# RGB_LED_2.net
KiCad netlist of a schematic drawn in Altium Designer
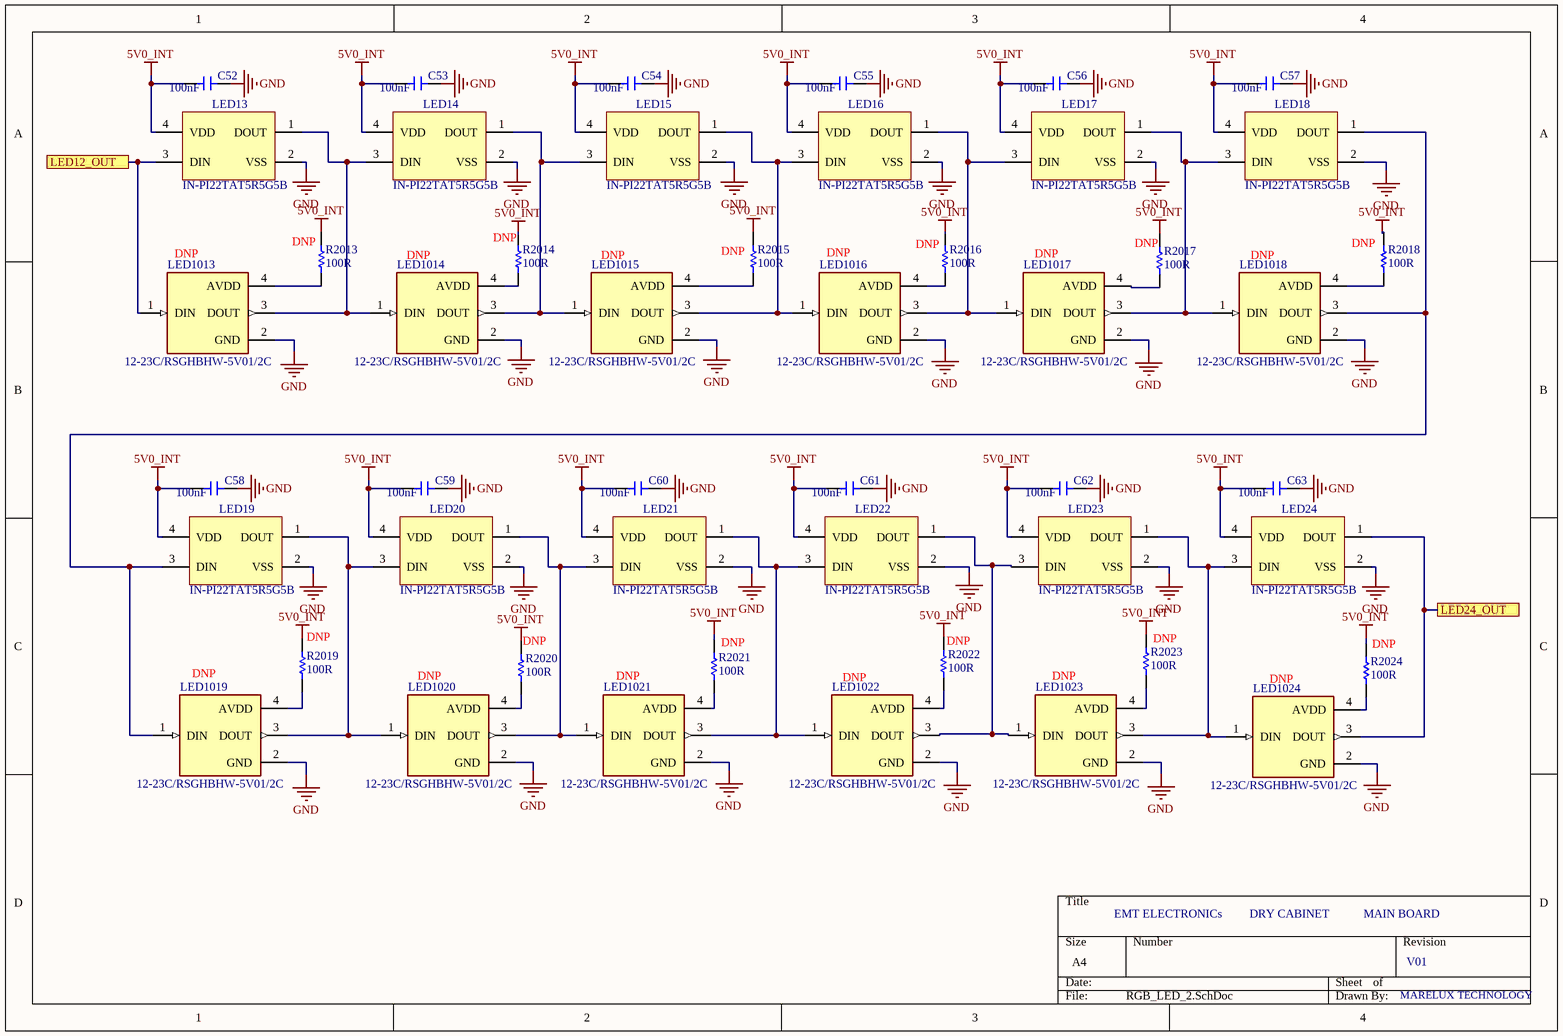
[diagram p0: RGB_LED_2.SchDoc]

(export (version "E")
  (design (tool "Eeschema 10.0.6"))
  (components
    (comp (ref "C52")
      (value "100nF")
      (footprint "MareLux24Lib:CAP_0402_CER")
      (description "100nF 0402 Ceramic Capacitor")
      (fields (field (name "PART NUMBER") "CL05B104KP5NNNC") (field (name "VOLTAGE") "10V"))
      (libsource (lib "MareLux24Lib") (part "CAP_GEN_CER"))
    )
    (comp (ref "C53")
      (value "100nF")
      (footprint "MareLux24Lib:CAP_0402_CER")
      (description "100nF 0402 Ceramic Capacitor")
      (fields (field (name "PART NUMBER") "CL05B104KP5NNNC") (field (name "VOLTAGE") "10V"))
      (libsource (lib "MareLux24Lib") (part "CAP_GEN_CER"))
    )
    (comp (ref "C54")
      (value "100nF")
      (footprint "MareLux24Lib:CAP_0402_CER")
      (description "100nF 0402 Ceramic Capacitor")
      (fields (field (name "PART NUMBER") "CL05B104KP5NNNC") (field (name "VOLTAGE") "10V"))
      (libsource (lib "MareLux24Lib") (part "CAP_GEN_CER"))
    )
    (comp (ref "C55")
      (value "100nF")
      (footprint "MareLux24Lib:CAP_0402_CER")
      (description "100nF 0402 Ceramic Capacitor")
      (fields (field (name "PART NUMBER") "CL05B104KP5NNNC") (field (name "VOLTAGE") "10V"))
      (libsource (lib "MareLux24Lib") (part "CAP_GEN_CER"))
    )
    (comp (ref "C56")
      (value "100nF")
      (footprint "MareLux24Lib:CAP_0402_CER")
      (description "100nF 0402 Ceramic Capacitor")
      (fields (field (name "PART NUMBER") "CL05B104KP5NNNC") (field (name "VOLTAGE") "10V"))
      (libsource (lib "MareLux24Lib") (part "CAP_GEN_CER"))
    )
    (comp (ref "C57")
      (value "100nF")
      (footprint "MareLux24Lib:CAP_0402_CER")
      (description "100nF 0402 Ceramic Capacitor")
      (fields (field (name "PART NUMBER") "CL05B104KP5NNNC") (field (name "VOLTAGE") "10V"))
      (libsource (lib "MareLux24Lib") (part "CAP_GEN_CER"))
    )
    (comp (ref "C58")
      (value "100nF")
      (footprint "MareLux24Lib:CAP_0402_CER")
      (description "100nF 0402 Ceramic Capacitor")
      (fields (field (name "PART NUMBER") "CL05B104KP5NNNC") (field (name "VOLTAGE") "10V"))
      (libsource (lib "MareLux24Lib") (part "CAP_GEN_CER"))
    )
    (comp (ref "C59")
      (value "100nF")
      (footprint "MareLux24Lib:CAP_0402_CER")
      (description "100nF 0402 Ceramic Capacitor")
      (fields (field (name "PART NUMBER") "CL05B104KP5NNNC") (field (name "VOLTAGE") "10V"))
      (libsource (lib "MareLux24Lib") (part "CAP_GEN_CER"))
    )
    (comp (ref "C60")
      (value "100nF")
      (footprint "MareLux24Lib:CAP_0402_CER")
      (description "100nF 0402 Ceramic Capacitor")
      (fields (field (name "PART NUMBER") "CL05B104KP5NNNC") (field (name "VOLTAGE") "10V"))
      (libsource (lib "MareLux24Lib") (part "CAP_GEN_CER"))
    )
    (comp (ref "C61")
      (value "100nF")
      (footprint "MareLux24Lib:CAP_0402_CER")
      (description "100nF 0402 Ceramic Capacitor")
      (fields (field (name "PART NUMBER") "CL05B104KP5NNNC") (field (name "VOLTAGE") "10V"))
      (libsource (lib "MareLux24Lib") (part "CAP_GEN_CER"))
    )
    (comp (ref "C62")
      (value "100nF")
      (footprint "MareLux24Lib:CAP_0402_CER")
      (description "100nF 0402 Ceramic Capacitor")
      (fields (field (name "PART NUMBER") "CL05B104KP5NNNC") (field (name "VOLTAGE") "10V"))
      (libsource (lib "MareLux24Lib") (part "CAP_GEN_CER"))
    )
    (comp (ref "C63")
      (value "100nF")
      (footprint "MareLux24Lib:CAP_0402_CER")
      (description "100nF 0402 Ceramic Capacitor")
      (fields (field (name "PART NUMBER") "CL05B104KP5NNNC") (field (name "VOLTAGE") "10V"))
      (libsource (lib "MareLux24Lib") (part "CAP_GEN_CER"))
    )
    (comp (ref "LED13")
      (value "IN-PI22TAT5R5G5B")
      (footprint "RGB_IN-PI22TAT5R5G5B")
      (description "ADDRESS LED DISCRETE SERIAL RGB")
      (fields (field (name "MANUFACTURER") "Inolux"))
      (libsource (lib "MareLux24Lib") (part "IN-PI22TAT5R5G5B"))
    )
    (comp (ref "LED14")
      (value "IN-PI22TAT5R5G5B")
      (footprint "RGB_IN-PI22TAT5R5G5B")
      (description "ADDRESS LED DISCRETE SERIAL RGB")
      (fields (field (name "MANUFACTURER") "Inolux"))
      (libsource (lib "MareLux24Lib") (part "IN-PI22TAT5R5G5B"))
    )
    (comp (ref "LED15")
      (value "IN-PI22TAT5R5G5B")
      (footprint "RGB_IN-PI22TAT5R5G5B")
      (description "ADDRESS LED DISCRETE SERIAL RGB")
      (fields (field (name "MANUFACTURER") "Inolux"))
      (libsource (lib "MareLux24Lib") (part "IN-PI22TAT5R5G5B"))
    )
    (comp (ref "LED16")
      (value "IN-PI22TAT5R5G5B")
      (footprint "RGB_IN-PI22TAT5R5G5B")
      (description "ADDRESS LED DISCRETE SERIAL RGB")
      (fields (field (name "MANUFACTURER") "Inolux"))
      (libsource (lib "MareLux24Lib") (part "IN-PI22TAT5R5G5B"))
    )
    (comp (ref "LED17")
      (value "IN-PI22TAT5R5G5B")
      (footprint "RGB_IN-PI22TAT5R5G5B")
      (description "ADDRESS LED DISCRETE SERIAL RGB")
      (fields (field (name "MANUFACTURER") "Inolux"))
      (libsource (lib "MareLux24Lib") (part "IN-PI22TAT5R5G5B"))
    )
    (comp (ref "LED18")
      (value "IN-PI22TAT5R5G5B")
      (footprint "RGB_IN-PI22TAT5R5G5B")
      (description "ADDRESS LED DISCRETE SERIAL RGB")
      (fields (field (name "MANUFACTURER") "Inolux"))
      (libsource (lib "MareLux24Lib") (part "IN-PI22TAT5R5G5B"))
    )
    (comp (ref "LED19")
      (value "IN-PI22TAT5R5G5B")
      (footprint "RGB_IN-PI22TAT5R5G5B")
      (description "ADDRESS LED DISCRETE SERIAL RGB")
      (fields (field (name "MANUFACTURER") "Inolux"))
      (libsource (lib "MareLux24Lib") (part "IN-PI22TAT5R5G5B"))
    )
    (comp (ref "LED20")
      (value "IN-PI22TAT5R5G5B")
      (footprint "RGB_IN-PI22TAT5R5G5B")
      (description "ADDRESS LED DISCRETE SERIAL RGB")
      (fields (field (name "MANUFACTURER") "Inolux"))
      (libsource (lib "MareLux24Lib") (part "IN-PI22TAT5R5G5B"))
    )
    (comp (ref "LED21")
      (value "IN-PI22TAT5R5G5B")
      (footprint "RGB_IN-PI22TAT5R5G5B")
      (description "ADDRESS LED DISCRETE SERIAL RGB")
      (fields (field (name "MANUFACTURER") "Inolux"))
      (libsource (lib "MareLux24Lib") (part "IN-PI22TAT5R5G5B"))
    )
    (comp (ref "LED22")
      (value "IN-PI22TAT5R5G5B")
      (footprint "RGB_IN-PI22TAT5R5G5B")
      (description "ADDRESS LED DISCRETE SERIAL RGB")
      (fields (field (name "MANUFACTURER") "Inolux"))
      (libsource (lib "MareLux24Lib") (part "IN-PI22TAT5R5G5B"))
    )
    (comp (ref "LED23")
      (value "IN-PI22TAT5R5G5B")
      (footprint "RGB_IN-PI22TAT5R5G5B")
      (description "ADDRESS LED DISCRETE SERIAL RGB")
      (fields (field (name "MANUFACTURER") "Inolux"))
      (libsource (lib "MareLux24Lib") (part "IN-PI22TAT5R5G5B"))
    )
    (comp (ref "LED24")
      (value "IN-PI22TAT5R5G5B")
      (footprint "RGB_IN-PI22TAT5R5G5B")
      (description "ADDRESS LED DISCRETE SERIAL RGB")
      (fields (field (name "MANUFACTURER") "Inolux"))
      (libsource (lib "MareLux24Lib") (part "IN-PI22TAT5R5G5B"))
    )
    (comp (ref "LED1013")
      (value "12-23C/RSGHBHW-5V01/2C")
      (footprint "LED_12-23C/RSGHBHW-5V01/2C")
      (fields (field (name "MF") "Everlight Electronics Co Ltd") (field (name "PLACE") "DNP"))
      (libsource (lib "12-23C_RSGHBHW-5V01_2C") (part "12-23C/RSGHBHW-5V01/2C"))
    )
    (comp (ref "LED1014")
      (value "12-23C/RSGHBHW-5V01/2C")
      (footprint "LED_12-23C/RSGHBHW-5V01/2C")
      (fields (field (name "MF") "Everlight Electronics Co Ltd") (field (name "PLACE") "DNP"))
      (libsource (lib "12-23C_RSGHBHW-5V01_2C") (part "12-23C/RSGHBHW-5V01/2C"))
    )
    (comp (ref "LED1015")
      (value "12-23C/RSGHBHW-5V01/2C")
      (footprint "LED_12-23C/RSGHBHW-5V01/2C")
      (fields (field (name "MF") "Everlight Electronics Co Ltd") (field (name "PLACE") "DNP"))
      (libsource (lib "12-23C_RSGHBHW-5V01_2C") (part "12-23C/RSGHBHW-5V01/2C"))
    )
    (comp (ref "LED1016")
      (value "12-23C/RSGHBHW-5V01/2C")
      (footprint "LED_12-23C/RSGHBHW-5V01/2C")
      (fields (field (name "MF") "Everlight Electronics Co Ltd") (field (name "PLACE") "DNP"))
      (libsource (lib "12-23C_RSGHBHW-5V01_2C") (part "12-23C/RSGHBHW-5V01/2C"))
    )
    (comp (ref "LED1017")
      (value "12-23C/RSGHBHW-5V01/2C")
      (footprint "LED_12-23C/RSGHBHW-5V01/2C")
      (fields (field (name "MF") "Everlight Electronics Co Ltd") (field (name "PLACE") "DNP"))
      (libsource (lib "12-23C_RSGHBHW-5V01_2C") (part "12-23C/RSGHBHW-5V01/2C"))
    )
    (comp (ref "LED1018")
      (value "12-23C/RSGHBHW-5V01/2C")
      (footprint "LED_12-23C/RSGHBHW-5V01/2C")
      (fields (field (name "MF") "Everlight Electronics Co Ltd") (field (name "PLACE") "DNP"))
      (libsource (lib "12-23C_RSGHBHW-5V01_2C") (part "12-23C/RSGHBHW-5V01/2C"))
    )
    (comp (ref "LED1019")
      (value "12-23C/RSGHBHW-5V01/2C")
      (footprint "LED_12-23C/RSGHBHW-5V01/2C")
      (fields (field (name "MF") "Everlight Electronics Co Ltd") (field (name "PLACE") "DNP"))
      (libsource (lib "12-23C_RSGHBHW-5V01_2C") (part "12-23C/RSGHBHW-5V01/2C"))
    )
    (comp (ref "LED1020")
      (value "12-23C/RSGHBHW-5V01/2C")
      (footprint "LED_12-23C/RSGHBHW-5V01/2C")
      (fields (field (name "MF") "Everlight Electronics Co Ltd") (field (name "PLACE") "DNP"))
      (libsource (lib "12-23C_RSGHBHW-5V01_2C") (part "12-23C/RSGHBHW-5V01/2C"))
    )
    (comp (ref "LED1021")
      (value "12-23C/RSGHBHW-5V01/2C")
      (footprint "LED_12-23C/RSGHBHW-5V01/2C")
      (fields (field (name "MF") "Everlight Electronics Co Ltd") (field (name "PLACE") "DNP"))
      (libsource (lib "12-23C_RSGHBHW-5V01_2C") (part "12-23C/RSGHBHW-5V01/2C"))
    )
    (comp (ref "LED1022")
      (value "12-23C/RSGHBHW-5V01/2C")
      (footprint "LED_12-23C/RSGHBHW-5V01/2C")
      (fields (field (name "MF") "Everlight Electronics Co Ltd") (field (name "PLACE") "DNP"))
      (libsource (lib "12-23C_RSGHBHW-5V01_2C") (part "12-23C/RSGHBHW-5V01/2C"))
    )
    (comp (ref "LED1023")
      (value "12-23C/RSGHBHW-5V01/2C")
      (footprint "LED_12-23C/RSGHBHW-5V01/2C")
      (fields (field (name "MF") "Everlight Electronics Co Ltd") (field (name "PLACE") "DNP"))
      (libsource (lib "12-23C_RSGHBHW-5V01_2C") (part "12-23C/RSGHBHW-5V01/2C"))
    )
    (comp (ref "LED1024")
      (value "12-23C/RSGHBHW-5V01/2C")
      (footprint "LED_12-23C/RSGHBHW-5V01/2C")
      (fields (field (name "MF") "Everlight Electronics Co Ltd") (field (name "PLACE") "DNP"))
      (libsource (lib "12-23C_RSGHBHW-5V01_2C") (part "12-23C/RSGHBHW-5V01/2C"))
    )
    (comp (ref "R2013")
      (value "100R")
      (footprint "MareLux24Lib:RES_0402_SMD")
      (description "Generic Chip Res 100R")
      (fields
        (field (name "PART NUMBER") "RMCF0402JT100R")
        (field (name "TOLERANCE") "5 %")
        (field (name "PLACE") "DNP")
      )
      (libsource (lib "MareLux24Lib") (part "RES_GEN_SMD"))
    )
    (comp (ref "R2014")
      (value "100R")
      (footprint "MareLux24Lib:RES_0402_SMD")
      (description "Generic Chip Res 100R")
      (fields
        (field (name "PART NUMBER") "RMCF0402JT100R")
        (field (name "TOLERANCE") "5 %")
        (field (name "PLACE") "DNP")
      )
      (libsource (lib "MareLux24Lib") (part "RES_GEN_SMD"))
    )
    (comp (ref "R2015")
      (value "100R")
      (footprint "MareLux24Lib:RES_0402_SMD")
      (description "Generic Chip Res 100R")
      (fields
        (field (name "PART NUMBER") "RMCF0402JT100R")
        (field (name "TOLERANCE") "5 %")
        (field (name "PLACE") "DNP")
      )
      (libsource (lib "MareLux24Lib") (part "RES_GEN_SMD"))
    )
    (comp (ref "R2016")
      (value "100R")
      (footprint "MareLux24Lib:RES_0402_SMD")
      (description "Generic Chip Res 100R")
      (fields
        (field (name "PART NUMBER") "RMCF0402JT100R")
        (field (name "TOLERANCE") "5 %")
        (field (name "PLACE") "DNP")
      )
      (libsource (lib "MareLux24Lib") (part "RES_GEN_SMD"))
    )
    (comp (ref "R2017")
      (value "100R")
      (footprint "MareLux24Lib:RES_0402_SMD")
      (description "Generic Chip Res 100R")
      (fields
        (field (name "PART NUMBER") "RMCF0402JT100R")
        (field (name "TOLERANCE") "5 %")
        (field (name "PLACE") "DNP")
      )
      (libsource (lib "MareLux24Lib") (part "RES_GEN_SMD"))
    )
    (comp (ref "R2018")
      (value "100R")
      (footprint "MareLux24Lib:RES_0402_SMD")
      (description "Generic Chip Res 100R")
      (fields
        (field (name "PART NUMBER") "RMCF0402JT100R")
        (field (name "TOLERANCE") "5 %")
        (field (name "PLACE") "DNP")
      )
      (libsource (lib "MareLux24Lib") (part "RES_GEN_SMD"))
    )
    (comp (ref "R2019")
      (value "100R")
      (footprint "MareLux24Lib:RES_0402_SMD")
      (description "Generic Chip Res 100R")
      (fields
        (field (name "PART NUMBER") "RMCF0402JT100R")
        (field (name "TOLERANCE") "5 %")
        (field (name "PLACE") "DNP")
      )
      (libsource (lib "MareLux24Lib") (part "RES_GEN_SMD"))
    )
    (comp (ref "R2020")
      (value "100R")
      (footprint "MareLux24Lib:RES_0402_SMD")
      (description "Generic Chip Res 100R")
      (fields
        (field (name "PART NUMBER") "RMCF0402JT100R")
        (field (name "TOLERANCE") "5 %")
        (field (name "PLACE") "DNP")
      )
      (libsource (lib "MareLux24Lib") (part "RES_GEN_SMD"))
    )
    (comp (ref "R2021")
      (value "100R")
      (footprint "MareLux24Lib:RES_0402_SMD")
      (description "Generic Chip Res 100R")
      (fields
        (field (name "PART NUMBER") "RMCF0402JT100R")
        (field (name "TOLERANCE") "5 %")
        (field (name "PLACE") "DNP")
      )
      (libsource (lib "MareLux24Lib") (part "RES_GEN_SMD"))
    )
    (comp (ref "R2022")
      (value "100R")
      (footprint "MareLux24Lib:RES_0402_SMD")
      (description "Generic Chip Res 100R")
      (fields
        (field (name "PART NUMBER") "RMCF0402JT100R")
        (field (name "TOLERANCE") "5 %")
        (field (name "PLACE") "DNP")
      )
      (libsource (lib "MareLux24Lib") (part "RES_GEN_SMD"))
    )
    (comp (ref "R2023")
      (value "100R")
      (footprint "MareLux24Lib:RES_0402_SMD")
      (description "Generic Chip Res 100R")
      (fields
        (field (name "PART NUMBER") "RMCF0402JT100R")
        (field (name "TOLERANCE") "5 %")
        (field (name "PLACE") "DNP")
      )
      (libsource (lib "MareLux24Lib") (part "RES_GEN_SMD"))
    )
    (comp (ref "R2024")
      (value "100R")
      (footprint "MareLux24Lib:RES_0402_SMD")
      (description "Generic Chip Res 100R")
      (fields
        (field (name "PART NUMBER") "RMCF0402JT100R")
        (field (name "TOLERANCE") "5 %")
        (field (name "PLACE") "DNP")
      )
      (libsource (lib "MareLux24Lib") (part "RES_GEN_SMD"))
    )
  )
  (nets
    (net (code "1") (name "/LED12_OUT") (class "Default")
      (node (ref "LED1013") (pin "1") (pinfunction "DIN_1") (pintype "input"))
      (node (ref "LED13") (pin "3") (pinfunction "DIN_3") (pintype "passive"))
    )
    (net (code "2") (name "/LED24_OUT") (class "Default")
      (node (ref "LED1024") (pin "3") (pinfunction "DOUT_3") (pintype "output"))
      (node (ref "LED24") (pin "1") (pinfunction "DOUT_1") (pintype "passive"))
    )
    (net (code "3") (name "5V0_INT") (class "Default")
      (node (ref "C52") (pin "2") (pinfunction "2_2") (pintype "passive"))
      (node (ref "C53") (pin "2") (pinfunction "2_2") (pintype "passive"))
      (node (ref "C54") (pin "2") (pinfunction "2_2") (pintype "passive"))
      (node (ref "C55") (pin "2") (pinfunction "2_2") (pintype "passive"))
      (node (ref "C56") (pin "2") (pinfunction "2_2") (pintype "passive"))
      (node (ref "C57") (pin "2") (pinfunction "2_2") (pintype "passive"))
      (node (ref "C58") (pin "2") (pinfunction "2_2") (pintype "passive"))
      (node (ref "C59") (pin "2") (pinfunction "2_2") (pintype "passive"))
      (node (ref "C60") (pin "2") (pinfunction "2_2") (pintype "passive"))
      (node (ref "C61") (pin "2") (pinfunction "2_2") (pintype "passive"))
      (node (ref "C62") (pin "2") (pinfunction "2_2") (pintype "passive"))
      (node (ref "C63") (pin "2") (pinfunction "2_2") (pintype "passive"))
      (node (ref "LED13") (pin "4") (pinfunction "VDD_4") (pintype "passive"))
      (node (ref "LED14") (pin "4") (pinfunction "VDD_4") (pintype "passive"))
      (node (ref "LED15") (pin "4") (pinfunction "VDD_4") (pintype "passive"))
      (node (ref "LED16") (pin "4") (pinfunction "VDD_4") (pintype "passive"))
      (node (ref "LED17") (pin "4") (pinfunction "VDD_4") (pintype "passive"))
      (node (ref "LED18") (pin "4") (pinfunction "VDD_4") (pintype "passive"))
      (node (ref "LED19") (pin "4") (pinfunction "VDD_4") (pintype "passive"))
      (node (ref "LED20") (pin "4") (pinfunction "VDD_4") (pintype "passive"))
      (node (ref "LED21") (pin "4") (pinfunction "VDD_4") (pintype "passive"))
      (node (ref "LED22") (pin "4") (pinfunction "VDD_4") (pintype "passive"))
      (node (ref "LED23") (pin "4") (pinfunction "VDD_4") (pintype "passive"))
      (node (ref "LED24") (pin "4") (pinfunction "VDD_4") (pintype "passive"))
      (node (ref "R2013") (pin "1") (pinfunction "1_1") (pintype "passive"))
      (node (ref "R2014") (pin "1") (pinfunction "1_1") (pintype "passive"))
      (node (ref "R2015") (pin "1") (pinfunction "1_1") (pintype "passive"))
      (node (ref "R2016") (pin "1") (pinfunction "1_1") (pintype "passive"))
      (node (ref "R2017") (pin "1") (pinfunction "1_1") (pintype "passive"))
      (node (ref "R2018") (pin "1") (pinfunction "1_1") (pintype "passive"))
      (node (ref "R2019") (pin "1") (pinfunction "1_1") (pintype "passive"))
      (node (ref "R2020") (pin "1") (pinfunction "1_1") (pintype "passive"))
      (node (ref "R2021") (pin "1") (pinfunction "1_1") (pintype "passive"))
      (node (ref "R2022") (pin "1") (pinfunction "1_1") (pintype "passive"))
      (node (ref "R2023") (pin "1") (pinfunction "1_1") (pintype "passive"))
      (node (ref "R2024") (pin "1") (pinfunction "1_1") (pintype "passive"))
    )
    (net (code "4") (name "GND") (class "Default")
      (node (ref "C52") (pin "1") (pinfunction "1_1") (pintype "passive"))
      (node (ref "C53") (pin "1") (pinfunction "1_1") (pintype "passive"))
      (node (ref "C54") (pin "1") (pinfunction "1_1") (pintype "passive"))
      (node (ref "C55") (pin "1") (pinfunction "1_1") (pintype "passive"))
      (node (ref "C56") (pin "1") (pinfunction "1_1") (pintype "passive"))
      (node (ref "C57") (pin "1") (pinfunction "1_1") (pintype "passive"))
      (node (ref "C58") (pin "1") (pinfunction "1_1") (pintype "passive"))
      (node (ref "C59") (pin "1") (pinfunction "1_1") (pintype "passive"))
      (node (ref "C60") (pin "1") (pinfunction "1_1") (pintype "passive"))
      (node (ref "C61") (pin "1") (pinfunction "1_1") (pintype "passive"))
      (node (ref "C62") (pin "1") (pinfunction "1_1") (pintype "passive"))
      (node (ref "C63") (pin "1") (pinfunction "1_1") (pintype "passive"))
      (node (ref "LED1013") (pin "2") (pinfunction "GND_2") (pintype "passive"))
      (node (ref "LED1014") (pin "2") (pinfunction "GND_2") (pintype "passive"))
      (node (ref "LED1015") (pin "2") (pinfunction "GND_2") (pintype "passive"))
      (node (ref "LED1016") (pin "2") (pinfunction "GND_2") (pintype "passive"))
      (node (ref "LED1017") (pin "2") (pinfunction "GND_2") (pintype "passive"))
      (node (ref "LED1018") (pin "2") (pinfunction "GND_2") (pintype "passive"))
      (node (ref "LED1019") (pin "2") (pinfunction "GND_2") (pintype "passive"))
      (node (ref "LED1020") (pin "2") (pinfunction "GND_2") (pintype "passive"))
      (node (ref "LED1021") (pin "2") (pinfunction "GND_2") (pintype "passive"))
      (node (ref "LED1022") (pin "2") (pinfunction "GND_2") (pintype "passive"))
      (node (ref "LED1023") (pin "2") (pinfunction "GND_2") (pintype "passive"))
      (node (ref "LED1024") (pin "2") (pinfunction "GND_2") (pintype "passive"))
      (node (ref "LED13") (pin "2") (pinfunction "VSS_2") (pintype "passive"))
      (node (ref "LED14") (pin "2") (pinfunction "VSS_2") (pintype "passive"))
      (node (ref "LED15") (pin "2") (pinfunction "VSS_2") (pintype "passive"))
      (node (ref "LED16") (pin "2") (pinfunction "VSS_2") (pintype "passive"))
      (node (ref "LED17") (pin "2") (pinfunction "VSS_2") (pintype "passive"))
      (node (ref "LED18") (pin "2") (pinfunction "VSS_2") (pintype "passive"))
      (node (ref "LED19") (pin "2") (pinfunction "VSS_2") (pintype "passive"))
      (node (ref "LED20") (pin "2") (pinfunction "VSS_2") (pintype "passive"))
      (node (ref "LED21") (pin "2") (pinfunction "VSS_2") (pintype "passive"))
      (node (ref "LED22") (pin "2") (pinfunction "VSS_2") (pintype "passive"))
      (node (ref "LED23") (pin "2") (pinfunction "VSS_2") (pintype "passive"))
      (node (ref "LED24") (pin "2") (pinfunction "VSS_2") (pintype "passive"))
    )
    (net (code "5") (name "Net-(LED1013-AVDD)") (class "Default")
      (node (ref "LED1013") (pin "4") (pinfunction "AVDD_4") (pintype "power_in"))
      (node (ref "R2013") (pin "2") (pinfunction "2_2") (pintype "passive"))
    )
    (net (code "6") (name "Net-(LED1013-DOUT)") (class "Default")
      (node (ref "LED1013") (pin "3") (pinfunction "DOUT_3") (pintype "output"))
      (node (ref "LED1014") (pin "1") (pinfunction "DIN_1") (pintype "input"))
      (node (ref "LED13") (pin "1") (pinfunction "DOUT_1") (pintype "passive"))
      (node (ref "LED14") (pin "3") (pinfunction "DIN_3") (pintype "passive"))
    )
    (net (code "7") (name "Net-(LED1014-AVDD)") (class "Default")
      (node (ref "LED1014") (pin "4") (pinfunction "AVDD_4") (pintype "power_in"))
      (node (ref "R2014") (pin "2") (pinfunction "2_2") (pintype "passive"))
    )
    (net (code "8") (name "Net-(LED1014-DOUT)") (class "Default")
      (node (ref "LED1014") (pin "3") (pinfunction "DOUT_3") (pintype "output"))
      (node (ref "LED1015") (pin "1") (pinfunction "DIN_1") (pintype "input"))
      (node (ref "LED14") (pin "1") (pinfunction "DOUT_1") (pintype "passive"))
      (node (ref "LED15") (pin "3") (pinfunction "DIN_3") (pintype "passive"))
    )
    (net (code "9") (name "Net-(LED1015-AVDD)") (class "Default")
      (node (ref "LED1015") (pin "4") (pinfunction "AVDD_4") (pintype "power_in"))
      (node (ref "R2015") (pin "2") (pinfunction "2_2") (pintype "passive"))
    )
    (net (code "10") (name "Net-(LED1015-DOUT)") (class "Default")
      (node (ref "LED1015") (pin "3") (pinfunction "DOUT_3") (pintype "output"))
      (node (ref "LED1016") (pin "1") (pinfunction "DIN_1") (pintype "input"))
      (node (ref "LED15") (pin "1") (pinfunction "DOUT_1") (pintype "passive"))
      (node (ref "LED16") (pin "3") (pinfunction "DIN_3") (pintype "passive"))
    )
    (net (code "11") (name "Net-(LED1016-AVDD)") (class "Default")
      (node (ref "LED1016") (pin "4") (pinfunction "AVDD_4") (pintype "power_in"))
      (node (ref "R2016") (pin "2") (pinfunction "2_2") (pintype "passive"))
    )
    (net (code "12") (name "Net-(LED1016-DOUT)") (class "Default")
      (node (ref "LED1016") (pin "3") (pinfunction "DOUT_3") (pintype "output"))
      (node (ref "LED1017") (pin "1") (pinfunction "DIN_1") (pintype "input"))
      (node (ref "LED16") (pin "1") (pinfunction "DOUT_1") (pintype "passive"))
      (node (ref "LED17") (pin "3") (pinfunction "DIN_3") (pintype "passive"))
    )
    (net (code "13") (name "Net-(LED1017-AVDD)") (class "Default")
      (node (ref "LED1017") (pin "4") (pinfunction "AVDD_4") (pintype "power_in"))
      (node (ref "R2017") (pin "2") (pinfunction "2_2") (pintype "passive"))
    )
    (net (code "14") (name "Net-(LED1017-DOUT)") (class "Default")
      (node (ref "LED1017") (pin "3") (pinfunction "DOUT_3") (pintype "output"))
      (node (ref "LED1018") (pin "1") (pinfunction "DIN_1") (pintype "input"))
      (node (ref "LED17") (pin "1") (pinfunction "DOUT_1") (pintype "passive"))
      (node (ref "LED18") (pin "3") (pinfunction "DIN_3") (pintype "passive"))
    )
    (net (code "15") (name "Net-(LED1018-AVDD)") (class "Default")
      (node (ref "LED1018") (pin "4") (pinfunction "AVDD_4") (pintype "power_in"))
      (node (ref "R2018") (pin "2") (pinfunction "2_2") (pintype "passive"))
    )
    (net (code "16") (name "Net-(LED1018-DOUT)") (class "Default")
      (node (ref "LED1018") (pin "3") (pinfunction "DOUT_3") (pintype "output"))
      (node (ref "LED1019") (pin "1") (pinfunction "DIN_1") (pintype "input"))
      (node (ref "LED18") (pin "1") (pinfunction "DOUT_1") (pintype "passive"))
      (node (ref "LED19") (pin "3") (pinfunction "DIN_3") (pintype "passive"))
    )
    (net (code "17") (name "Net-(LED1019-AVDD)") (class "Default")
      (node (ref "LED1019") (pin "4") (pinfunction "AVDD_4") (pintype "power_in"))
      (node (ref "R2019") (pin "2") (pinfunction "2_2") (pintype "passive"))
    )
    (net (code "18") (name "Net-(LED1019-DOUT)") (class "Default")
      (node (ref "LED1019") (pin "3") (pinfunction "DOUT_3") (pintype "output"))
      (node (ref "LED1020") (pin "1") (pinfunction "DIN_1") (pintype "input"))
      (node (ref "LED19") (pin "1") (pinfunction "DOUT_1") (pintype "passive"))
      (node (ref "LED20") (pin "3") (pinfunction "DIN_3") (pintype "passive"))
    )
    (net (code "19") (name "Net-(LED1020-AVDD)") (class "Default")
      (node (ref "LED1020") (pin "4") (pinfunction "AVDD_4") (pintype "power_in"))
      (node (ref "R2020") (pin "2") (pinfunction "2_2") (pintype "passive"))
    )
    (net (code "20") (name "Net-(LED1020-DOUT)") (class "Default")
      (node (ref "LED1020") (pin "3") (pinfunction "DOUT_3") (pintype "output"))
      (node (ref "LED1021") (pin "1") (pinfunction "DIN_1") (pintype "input"))
      (node (ref "LED20") (pin "1") (pinfunction "DOUT_1") (pintype "passive"))
      (node (ref "LED21") (pin "3") (pinfunction "DIN_3") (pintype "passive"))
    )
    (net (code "21") (name "Net-(LED1021-AVDD)") (class "Default")
      (node (ref "LED1021") (pin "4") (pinfunction "AVDD_4") (pintype "power_in"))
      (node (ref "R2021") (pin "2") (pinfunction "2_2") (pintype "passive"))
    )
    (net (code "22") (name "Net-(LED1021-DOUT)") (class "Default")
      (node (ref "LED1021") (pin "3") (pinfunction "DOUT_3") (pintype "output"))
      (node (ref "LED1022") (pin "1") (pinfunction "DIN_1") (pintype "input"))
      (node (ref "LED21") (pin "1") (pinfunction "DOUT_1") (pintype "passive"))
      (node (ref "LED22") (pin "3") (pinfunction "DIN_3") (pintype "passive"))
    )
    (net (code "23") (name "Net-(LED1022-AVDD)") (class "Default")
      (node (ref "LED1022") (pin "4") (pinfunction "AVDD_4") (pintype "power_in"))
      (node (ref "R2022") (pin "2") (pinfunction "2_2") (pintype "passive"))
    )
    (net (code "24") (name "Net-(LED1022-DOUT)") (class "Default")
      (node (ref "LED1022") (pin "3") (pinfunction "DOUT_3") (pintype "output"))
      (node (ref "LED1023") (pin "1") (pinfunction "DIN_1") (pintype "input"))
      (node (ref "LED22") (pin "1") (pinfunction "DOUT_1") (pintype "passive"))
      (node (ref "LED23") (pin "3") (pinfunction "DIN_3") (pintype "passive"))
    )
    (net (code "25") (name "Net-(LED1023-AVDD)") (class "Default")
      (node (ref "LED1023") (pin "4") (pinfunction "AVDD_4") (pintype "power_in"))
      (node (ref "R2023") (pin "2") (pinfunction "2_2") (pintype "passive"))
    )
    (net (code "26") (name "Net-(LED1023-DOUT)") (class "Default")
      (node (ref "LED1023") (pin "3") (pinfunction "DOUT_3") (pintype "output"))
      (node (ref "LED1024") (pin "1") (pinfunction "DIN_1") (pintype "input"))
      (node (ref "LED23") (pin "1") (pinfunction "DOUT_1") (pintype "passive"))
      (node (ref "LED24") (pin "3") (pinfunction "DIN_3") (pintype "passive"))
    )
    (net (code "27") (name "Net-(LED1024-AVDD)") (class "Default")
      (node (ref "LED1024") (pin "4") (pinfunction "AVDD_4") (pintype "power_in"))
      (node (ref "R2024") (pin "2") (pinfunction "2_2") (pintype "passive"))
    )
  )
)
